# ACAC.net
KiCad netlist of a schematic drawn in EasyEDA Pro
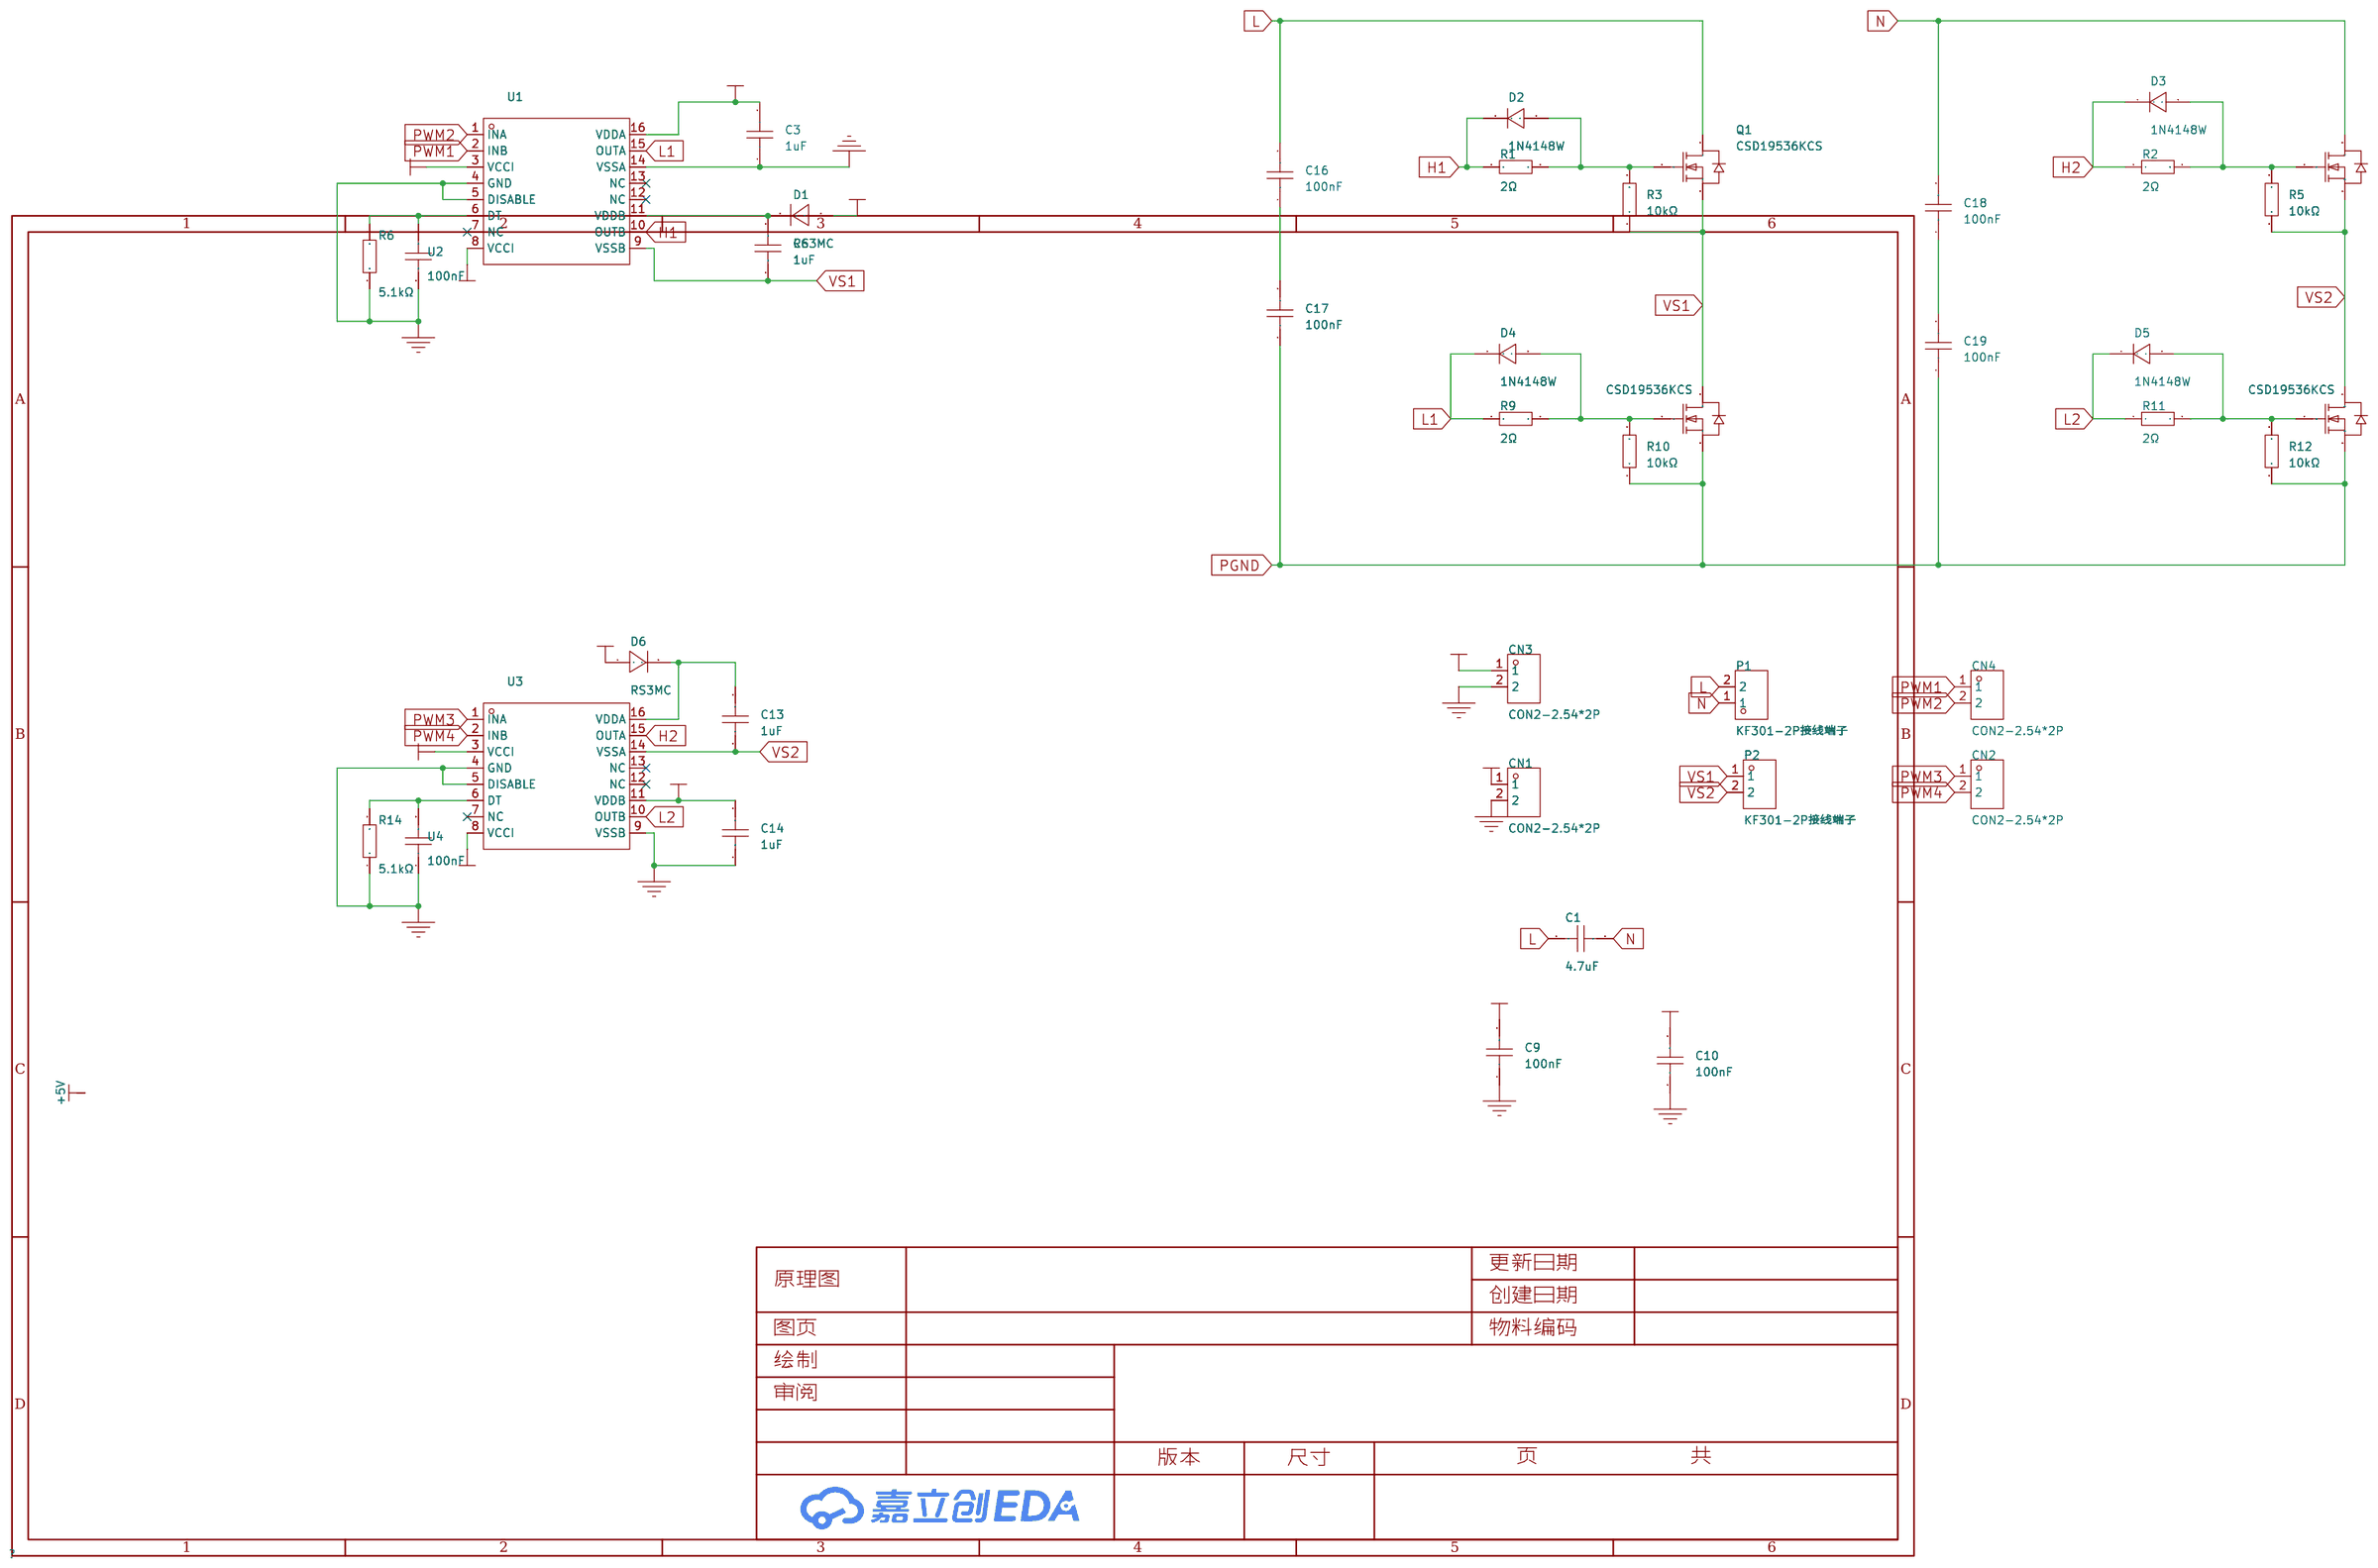
[diagram p0: schematic sheet]

(export (version "E")
  (design (tool "Eeschema 10.0.6"))
  (components
    (comp (ref "C1")
      (value "4.7uF")
      (footprint "easyedapro:CAP-TH_L27.5-W12.0-P25.00-D1.0")
      (description "容值:4.7uF;精度:±10%;额定电压:400V;工作温度:-40°C~+100°C;")
      (fields (field (name "Manufacturer Part") "KP475K2G2501") (field (name "Manufacturer") "KYET(科雅)"))
      (libsource (lib "easyedapro") (part "KP475K2G2501"))
    )
    (comp (ref "C3")
      (value "1uF")
      (footprint "easyedapro:C0805")
      (libsource (lib "easyedapro") (part "CapAcitance"))
    )
    (comp (ref "C6")
      (value "1uF")
      (footprint "easyedapro:C0805")
      (libsource (lib "easyedapro") (part "CapAcitance"))
    )
    (comp (ref "C9")
      (value "100nF")
      (footprint "easyedapro:C0805")
      (libsource (lib "easyedapro") (part "CapAcitance"))
    )
    (comp (ref "C10")
      (value "100nF")
      (footprint "easyedapro:C0805")
      (libsource (lib "easyedapro") (part "CapAcitance"))
    )
    (comp (ref "C13")
      (value "1uF")
      (footprint "easyedapro:C0805")
      (libsource (lib "easyedapro") (part "CapAcitance"))
    )
    (comp (ref "C14")
      (value "1uF")
      (footprint "easyedapro:C0805")
      (libsource (lib "easyedapro") (part "CapAcitance"))
    )
    (comp (ref "C16")
      (value "100nF")
      (footprint "easyedapro:C0805")
      (libsource (lib "easyedapro") (part "CapAcitance"))
    )
    (comp (ref "C17")
      (value "100nF")
      (footprint "easyedapro:C0805")
      (libsource (lib "easyedapro") (part "CapAcitance"))
    )
    (comp (ref "C18")
      (value "100nF")
      (footprint "easyedapro:C0805")
      (libsource (lib "easyedapro") (part "CapAcitance"))
    )
    (comp (ref "C19")
      (value "100nF")
      (footprint "easyedapro:C0805")
      (libsource (lib "easyedapro") (part "CapAcitance"))
    )
    (comp (ref "CN1")
      (value "CON2-2.54*2P")
      (footprint "easyedapro:CONN-TH_2P-P2.54-V")
      (libsource (lib "easyedapro") (part "CON2-2.54*2P"))
    )
    (comp (ref "CN2")
      (value "CON2-2.54*2P")
      (footprint "easyedapro:CONN-TH_2P-P2.54-V")
      (libsource (lib "easyedapro") (part "CON2-2.54*2P"))
    )
    (comp (ref "CN3")
      (value "CON2-2.54*2P")
      (footprint "easyedapro:CONN-TH_2P-P2.54-V")
      (libsource (lib "easyedapro") (part "CON2-2.54*2P"))
    )
    (comp (ref "CN4")
      (value "CON2-2.54*2P")
      (footprint "easyedapro:CONN-TH_2P-P2.54-V")
      (libsource (lib "easyedapro") (part "CON2-2.54*2P"))
    )
    (comp (ref "D1")
      (value "RS3MC")
      (footprint "easyedapro:SMC_L7.1-W6.2-LS8.1-R-RD")
      (description "二极管配置:独立式;正向压降(Vf):1.3V@3A;直流反向耐压(Vr):1kV;整流电流:3A;反向恢复时间(trr):500ns;")
      (fields (field (name "Manufacturer") "MDD(辰达半导体)"))
      (libsource (lib "easyedapro") (part "RS3M_C15283"))
    )
    (comp (ref "D2")
      (value "1N4148W")
      (footprint "easyedapro:SOD-123F_L2.7-W1.6-LS3.8-RD")
      (description "二极管配置:独立式;正向压降(Vf):1V@50mA;直流反向耐压(Vr):75V;平均整流电流(Io):150mA;功率:400mW;反向恢复时间(trr):4ns;")
      (fields (field (name "Manufacturer") "ST(先科)"))
      (libsource (lib "easyedapro") (part "1N4148W_C81598"))
    )
    (comp (ref "D3")
      (value "1N4148W")
      (footprint "easyedapro:SOD-123F_L2.7-W1.6-LS3.8-RD")
      (description "二极管配置:独立式;正向压降(Vf):1V@50mA;直流反向耐压(Vr):75V;平均整流电流(Io):150mA;功率:400mW;反向恢复时间(trr):4ns;")
      (fields (field (name "Manufacturer") "ST(先科)"))
      (libsource (lib "easyedapro") (part "1N4148W_C81598"))
    )
    (comp (ref "D4")
      (value "1N4148W")
      (footprint "easyedapro:SOD-123F_L2.7-W1.6-LS3.8-RD")
      (description "二极管配置:独立式;正向压降(Vf):1V@50mA;直流反向耐压(Vr):75V;平均整流电流(Io):150mA;功率:400mW;反向恢复时间(trr):4ns;")
      (fields (field (name "Manufacturer") "ST(先科)"))
      (libsource (lib "easyedapro") (part "1N4148W_C81598"))
    )
    (comp (ref "D5")
      (value "1N4148W")
      (footprint "easyedapro:SOD-123F_L2.7-W1.6-LS3.8-RD")
      (description "二极管配置:独立式;正向压降(Vf):1V@50mA;直流反向耐压(Vr):75V;平均整流电流(Io):150mA;功率:400mW;反向恢复时间(trr):4ns;")
      (fields (field (name "Manufacturer") "ST(先科)"))
      (libsource (lib "easyedapro") (part "1N4148W_C81598"))
    )
    (comp (ref "D6")
      (value "RS3MC")
      (footprint "easyedapro:SMC_L7.1-W6.2-LS8.1-R-RD")
      (description "二极管配置:独立式;正向压降(Vf):1.3V@3A;直流反向耐压(Vr):1kV;整流电流:3A;反向恢复时间(trr):500ns;")
      (fields (field (name "Manufacturer") "MDD(辰达半导体)"))
      (libsource (lib "easyedapro") (part "RS3M_C15283"))
    )
    (comp (ref "P1")
      (value "KF301-2P接线端子")
      (footprint "easyedapro:CONN-TH_XY301V-A-5.0-2P")
      (libsource (lib "easyedapro") (part "KF301-2P接线端子"))
    )
    (comp (ref "P2")
      (value "KF301-2P接线端子")
      (footprint "easyedapro:CONN-TH_XY301V-A-5.0-2P")
      (libsource (lib "easyedapro") (part "KF301-2P接线端子"))
    )
    (comp (ref "Q1")
      (value "CSD19536KCS")
      (footprint "easyedapro:TO-220-3_L10.0-W4.5-P2.54-L")
      (fields (field (name "Manufacturer") "TI(德州仪器)"))
      (libsource (lib "easyedapro") (part "CSD19536KCS"))
    )
    (comp (ref "Q2")
      (value "CSD19536KCS")
      (footprint "easyedapro:TO-220-3_L10.0-W4.5-P2.54-L")
      (fields (field (name "Manufacturer") "TI(德州仪器)"))
      (libsource (lib "easyedapro") (part "CSD19536KCS"))
    )
    (comp (ref "Q3")
      (value "CSD19536KCS")
      (footprint "easyedapro:TO-220-3_L10.0-W4.5-P2.54-L")
      (fields (field (name "Manufacturer") "TI(德州仪器)"))
      (libsource (lib "easyedapro") (part "CSD19536KCS"))
    )
    (comp (ref "Q4")
      (value "CSD19536KCS")
      (footprint "easyedapro:TO-220-3_L10.0-W4.5-P2.54-L")
      (fields (field (name "Manufacturer") "TI(德州仪器)"))
      (libsource (lib "easyedapro") (part "CSD19536KCS"))
    )
    (comp (ref "R1")
      (value "2Ω")
      (footprint "easyedapro:Res_1/8W")
      (libsource (lib "easyedapro") (part "电阻"))
    )
    (comp (ref "R2")
      (value "2Ω")
      (footprint "easyedapro:Res_1/8W")
      (libsource (lib "easyedapro") (part "电阻"))
    )
    (comp (ref "R3")
      (value "10kΩ")
      (footprint "easyedapro:Res_1/8W")
      (libsource (lib "easyedapro") (part "电阻"))
    )
    (comp (ref "R5")
      (value "10kΩ")
      (footprint "easyedapro:Res_1/8W")
      (libsource (lib "easyedapro") (part "电阻"))
    )
    (comp (ref "R6")
      (value "20kΩ")
      (footprint "easyedapro:RES-TH_BD2.4-L6.3-P10.30-D0.6")
      (description "电阻类型:金属膜电阻;阻值:20kΩ;精度:±1%;功率:500mW;温度系数:±50ppm/℃;")
      (fields (field (name "Manufacturer Part") "MFR50SFTE52-20K") (field (name "Manufacturer") "YAGEO(国巨)"))
      (libsource (lib "easyedapro") (part "MFR50SFTE52-20K"))
    )
    (comp (ref "R9")
      (value "2Ω")
      (footprint "easyedapro:Res_1/8W")
      (libsource (lib "easyedapro") (part "电阻"))
    )
    (comp (ref "R10")
      (value "10kΩ")
      (footprint "easyedapro:Res_1/8W")
      (libsource (lib "easyedapro") (part "电阻"))
    )
    (comp (ref "R11")
      (value "2Ω")
      (footprint "easyedapro:Res_1/8W")
      (libsource (lib "easyedapro") (part "电阻"))
    )
    (comp (ref "R12")
      (value "10kΩ")
      (footprint "easyedapro:Res_1/8W")
      (libsource (lib "easyedapro") (part "电阻"))
    )
    (comp (ref "R14")
      (value "20kΩ")
      (footprint "easyedapro:RES-TH_BD2.4-L6.3-P10.30-D0.6")
      (description "电阻类型:金属膜电阻;阻值:20kΩ;精度:±1%;功率:500mW;温度系数:±50ppm/℃;")
      (fields (field (name "Manufacturer Part") "MFR50SFTE52-20K") (field (name "Manufacturer") "YAGEO(国巨)"))
      (libsource (lib "easyedapro") (part "MFR50SFTE52-20K"))
    )
    (comp (ref "U1")
      (value "UCC21520")
      (footprint "easyedapro:SOIC-16_L10.3-W7.5-P1.27-LS10.3-BL")
      (fields (field (name "Manufacturer") "TI(德州仪器)"))
      (libsource (lib "easyedapro") (part "UCC21520"))
    )
    (comp (ref "U2")
      (value "100nF")
      (footprint "easyedapro:CAP-TH_L5.1-W3.2-P6.35-D0.5")
      (description "容值:47nF;精度:±10%;额定电压:100V;温度系数:X7R;")
      (fields (field (name "Manufacturer Part") "1C25X7R473K100B") (field (name "Manufacturer") "VISHAY(威世)"))
      (libsource (lib "easyedapro") (part "1C25X7R473K100B"))
    )
    (comp (ref "U3")
      (value "UCC21520")
      (footprint "easyedapro:SOIC-16_L10.3-W7.5-P1.27-LS10.3-BL")
      (fields (field (name "Manufacturer") "TI(德州仪器)"))
      (libsource (lib "easyedapro") (part "UCC21520"))
    )
    (comp (ref "U4")
      (value "100nF")
      (footprint "easyedapro:CAP-TH_L5.1-W3.2-P6.35-D0.5")
      (description "容值:47nF;精度:±10%;额定电压:100V;温度系数:X7R;")
      (fields (field (name "Manufacturer Part") "1C25X7R473K100B") (field (name "Manufacturer") "VISHAY(威世)"))
      (libsource (lib "easyedapro") (part "1C25X7R473K100B"))
    )
  )
  (nets
    (net (code "1") (name "+5V") (class "Default")
      (node (ref "C9") (pin "2") (pinfunction "2_2") (pintype "input"))
      (node (ref "CN1") (pin "1") (pinfunction "1_1") (pintype "unspecified"))
      (node (ref "U1") (pin "3") (pinfunction "VCCI_3") (pintype "unspecified"))
      (node (ref "U1") (pin "8") (pinfunction "VCCI_8") (pintype "unspecified"))
      (node (ref "U3") (pin "3") (pinfunction "VCCI_3") (pintype "unspecified"))
      (node (ref "U3") (pin "8") (pinfunction "VCCI_8") (pintype "unspecified"))
    )
    (net (code "2") (name "+12V") (class "Default")
      (node (ref "C10") (pin "2") (pinfunction "2_2") (pintype "input"))
      (node (ref "C14") (pin "2") (pinfunction "2_2") (pintype "input"))
      (node (ref "C3") (pin "2") (pinfunction "2_2") (pintype "input"))
      (node (ref "CN3") (pin "1") (pinfunction "1_1") (pintype "unspecified"))
      (node (ref "D1") (pin "1") (pinfunction "A_1") (pintype "unspecified"))
      (node (ref "D6") (pin "1") (pinfunction "A_1") (pintype "unspecified"))
      (node (ref "U1") (pin "16") (pinfunction "VDDA_16") (pintype "unspecified"))
      (node (ref "U3") (pin "11") (pinfunction "VDDB_11") (pintype "unspecified"))
    )
    (net (code "3") (name "DGND") (class "Default")
      (node (ref "C9") (pin "1") (pinfunction "1_1") (pintype "input"))
      (node (ref "CN1") (pin "2") (pinfunction "2_2") (pintype "unspecified"))
      (node (ref "R14") (pin "1") (pinfunction "1_1") (pintype "unspecified"))
      (node (ref "R6") (pin "1") (pinfunction "1_1") (pintype "unspecified"))
      (node (ref "U1") (pin "4") (pinfunction "GND_4") (pintype "unspecified"))
      (node (ref "U1") (pin "5") (pinfunction "DISABLE_5") (pintype "unspecified"))
      (node (ref "U2") (pin "1") (pinfunction "1_1") (pintype "unspecified"))
      (node (ref "U3") (pin "4") (pinfunction "GND_4") (pintype "unspecified"))
      (node (ref "U3") (pin "5") (pinfunction "DISABLE_5") (pintype "unspecified"))
      (node (ref "U4") (pin "1") (pinfunction "1_1") (pintype "unspecified"))
    )
    (net (code "4") (name "H1") (class "Default")
      (node (ref "D2") (pin "1") (pinfunction "K_1") (pintype "unspecified"))
      (node (ref "R1") (pin "1") (pinfunction "1_1") (pintype "input"))
      (node (ref "U1") (pin "10") (pinfunction "OUTB_10") (pintype "unspecified"))
    )
    (net (code "5") (name "H2") (class "Default")
      (node (ref "D3") (pin "1") (pinfunction "K_1") (pintype "unspecified"))
      (node (ref "R2") (pin "1") (pinfunction "1_1") (pintype "input"))
      (node (ref "U3") (pin "15") (pinfunction "OUTA_15") (pintype "unspecified"))
    )
    (net (code "6") (name "L") (class "Default")
      (node (ref "C1") (pin "2") (pinfunction "2_2") (pintype "unspecified"))
      (node (ref "C16") (pin "2") (pinfunction "2_2") (pintype "input"))
      (node (ref "P1") (pin "2") (pinfunction "2_2") (pintype "unspecified"))
      (node (ref "Q1") (pin "2") (pinfunction "D_2") (pintype "unspecified"))
    )
    (net (code "7") (name "L1") (class "Default")
      (node (ref "D4") (pin "1") (pinfunction "K_1") (pintype "unspecified"))
      (node (ref "R9") (pin "1") (pinfunction "1_1") (pintype "input"))
      (node (ref "U1") (pin "15") (pinfunction "OUTA_15") (pintype "unspecified"))
    )
    (net (code "8") (name "L2") (class "Default")
      (node (ref "D5") (pin "1") (pinfunction "K_1") (pintype "unspecified"))
      (node (ref "R11") (pin "1") (pinfunction "1_1") (pintype "input"))
      (node (ref "U3") (pin "10") (pinfunction "OUTB_10") (pintype "unspecified"))
    )
    (net (code "9") (name "N") (class "Default")
      (node (ref "C1") (pin "1") (pinfunction "1_1") (pintype "unspecified"))
      (node (ref "C18") (pin "2") (pinfunction "2_2") (pintype "input"))
      (node (ref "P1") (pin "1") (pinfunction "1_1") (pintype "unspecified"))
      (node (ref "Q2") (pin "2") (pinfunction "D_2") (pintype "unspecified"))
    )
    (net (code "10") (name "Net-(C16-Pad1)") (class "Default")
      (node (ref "C16") (pin "1") (pinfunction "1_1") (pintype "input"))
      (node (ref "C17") (pin "2") (pinfunction "2_2") (pintype "input"))
    )
    (net (code "11") (name "Net-(C18-Pad1)") (class "Default")
      (node (ref "C18") (pin "1") (pinfunction "1_1") (pintype "input"))
      (node (ref "C19") (pin "2") (pinfunction "2_2") (pintype "input"))
    )
    (net (code "12") (name "Net-(D1-K)") (class "Default")
      (node (ref "C6") (pin "2") (pinfunction "2_2") (pintype "input"))
      (node (ref "D1") (pin "2") (pinfunction "K_2") (pintype "unspecified"))
      (node (ref "U1") (pin "11") (pinfunction "VDDB_11") (pintype "unspecified"))
    )
    (net (code "13") (name "Net-(D2-A)") (class "Default")
      (node (ref "D2") (pin "2") (pinfunction "A_2") (pintype "unspecified"))
      (node (ref "Q1") (pin "1") (pinfunction "G_1") (pintype "unspecified"))
      (node (ref "R1") (pin "2") (pinfunction "2_2") (pintype "input"))
      (node (ref "R3") (pin "2") (pinfunction "2_2") (pintype "input"))
    )
    (net (code "14") (name "Net-(D3-A)") (class "Default")
      (node (ref "D3") (pin "2") (pinfunction "A_2") (pintype "unspecified"))
      (node (ref "Q2") (pin "1") (pinfunction "G_1") (pintype "unspecified"))
      (node (ref "R2") (pin "2") (pinfunction "2_2") (pintype "input"))
      (node (ref "R5") (pin "2") (pinfunction "2_2") (pintype "input"))
    )
    (net (code "15") (name "Net-(D4-A)") (class "Default")
      (node (ref "D4") (pin "2") (pinfunction "A_2") (pintype "unspecified"))
      (node (ref "Q3") (pin "1") (pinfunction "G_1") (pintype "unspecified"))
      (node (ref "R10") (pin "2") (pinfunction "2_2") (pintype "input"))
      (node (ref "R9") (pin "2") (pinfunction "2_2") (pintype "input"))
    )
    (net (code "16") (name "Net-(D5-A)") (class "Default")
      (node (ref "D5") (pin "2") (pinfunction "A_2") (pintype "unspecified"))
      (node (ref "Q4") (pin "1") (pinfunction "G_1") (pintype "unspecified"))
      (node (ref "R11") (pin "2") (pinfunction "2_2") (pintype "input"))
      (node (ref "R12") (pin "2") (pinfunction "2_2") (pintype "input"))
    )
    (net (code "17") (name "Net-(D6-K)") (class "Default")
      (node (ref "C13") (pin "2") (pinfunction "2_2") (pintype "input"))
      (node (ref "D6") (pin "2") (pinfunction "K_2") (pintype "unspecified"))
      (node (ref "U3") (pin "16") (pinfunction "VDDA_16") (pintype "unspecified"))
    )
    (net (code "18") (name "Net-(U1-DT)") (class "Default")
      (node (ref "R6") (pin "2") (pinfunction "2_2") (pintype "unspecified"))
      (node (ref "U1") (pin "6") (pinfunction "DT_6") (pintype "unspecified"))
      (node (ref "U2") (pin "2") (pinfunction "2_2") (pintype "unspecified"))
    )
    (net (code "19") (name "Net-(U3-DT)") (class "Default")
      (node (ref "R14") (pin "2") (pinfunction "2_2") (pintype "unspecified"))
      (node (ref "U3") (pin "6") (pinfunction "DT_6") (pintype "unspecified"))
      (node (ref "U4") (pin "2") (pinfunction "2_2") (pintype "unspecified"))
    )
    (net (code "20") (name "PGND") (class "Default")
      (node (ref "C10") (pin "1") (pinfunction "1_1") (pintype "input"))
      (node (ref "C14") (pin "1") (pinfunction "1_1") (pintype "input"))
      (node (ref "C17") (pin "1") (pinfunction "1_1") (pintype "input"))
      (node (ref "C19") (pin "1") (pinfunction "1_1") (pintype "input"))
      (node (ref "C3") (pin "1") (pinfunction "1_1") (pintype "input"))
      (node (ref "CN3") (pin "2") (pinfunction "2_2") (pintype "unspecified"))
      (node (ref "Q3") (pin "3") (pinfunction "S_3") (pintype "unspecified"))
      (node (ref "Q4") (pin "3") (pinfunction "S_3") (pintype "unspecified"))
      (node (ref "R10") (pin "1") (pinfunction "1_1") (pintype "input"))
      (node (ref "R12") (pin "1") (pinfunction "1_1") (pintype "input"))
      (node (ref "U1") (pin "14") (pinfunction "VSSA_14") (pintype "unspecified"))
      (node (ref "U3") (pin "9") (pinfunction "VSSB_9") (pintype "unspecified"))
    )
    (net (code "21") (name "PWM1") (class "Default")
      (node (ref "CN4") (pin "1") (pinfunction "1_1") (pintype "unspecified"))
      (node (ref "U1") (pin "2") (pinfunction "INB_2") (pintype "unspecified"))
    )
    (net (code "22") (name "PWM2") (class "Default")
      (node (ref "CN4") (pin "2") (pinfunction "2_2") (pintype "unspecified"))
      (node (ref "U1") (pin "1") (pinfunction "INA_1") (pintype "unspecified"))
    )
    (net (code "23") (name "PWM3") (class "Default")
      (node (ref "CN2") (pin "1") (pinfunction "1_1") (pintype "unspecified"))
      (node (ref "U3") (pin "1") (pinfunction "INA_1") (pintype "unspecified"))
    )
    (net (code "24") (name "PWM4") (class "Default")
      (node (ref "CN2") (pin "2") (pinfunction "2_2") (pintype "unspecified"))
      (node (ref "U3") (pin "2") (pinfunction "INB_2") (pintype "unspecified"))
    )
    (net (code "25") (name "VS1") (class "Default")
      (node (ref "C6") (pin "1") (pinfunction "1_1") (pintype "input"))
      (node (ref "P2") (pin "1") (pinfunction "1_1") (pintype "unspecified"))
      (node (ref "Q1") (pin "3") (pinfunction "S_3") (pintype "unspecified"))
      (node (ref "Q3") (pin "2") (pinfunction "D_2") (pintype "unspecified"))
      (node (ref "R3") (pin "1") (pinfunction "1_1") (pintype "input"))
      (node (ref "U1") (pin "9") (pinfunction "VSSB_9") (pintype "unspecified"))
    )
    (net (code "26") (name "VS2") (class "Default")
      (node (ref "C13") (pin "1") (pinfunction "1_1") (pintype "input"))
      (node (ref "P2") (pin "2") (pinfunction "2_2") (pintype "unspecified"))
      (node (ref "Q2") (pin "3") (pinfunction "S_3") (pintype "unspecified"))
      (node (ref "Q4") (pin "2") (pinfunction "D_2") (pintype "unspecified"))
      (node (ref "R5") (pin "1") (pinfunction "1_1") (pintype "input"))
      (node (ref "U3") (pin "14") (pinfunction "VSSA_14") (pintype "unspecified"))
    )
    (net (code "27") (name "unconnected-(U1-NC-Pad7)") (class "Default")
      (node (ref "U1") (pin "7") (pinfunction "NC_7") (pintype "unspecified+no_connect"))
    )
    (net (code "28") (name "unconnected-(U1-NC-Pad12)") (class "Default")
      (node (ref "U1") (pin "12") (pinfunction "NC_12") (pintype "unspecified+no_connect"))
    )
    (net (code "29") (name "unconnected-(U1-NC-Pad13)") (class "Default")
      (node (ref "U1") (pin "13") (pinfunction "NC_13") (pintype "unspecified+no_connect"))
    )
    (net (code "30") (name "unconnected-(U3-NC-Pad7)") (class "Default")
      (node (ref "U3") (pin "7") (pinfunction "NC_7") (pintype "unspecified+no_connect"))
    )
    (net (code "31") (name "unconnected-(U3-NC-Pad12)") (class "Default")
      (node (ref "U3") (pin "12") (pinfunction "NC_12") (pintype "unspecified+no_connect"))
    )
    (net (code "32") (name "unconnected-(U3-NC-Pad13)") (class "Default")
      (node (ref "U3") (pin "13") (pinfunction "NC_13") (pintype "unspecified+no_connect"))
    )
  )
)
